# TX_Board.net
KiCad netlist of a schematic drawn in Altium Designer
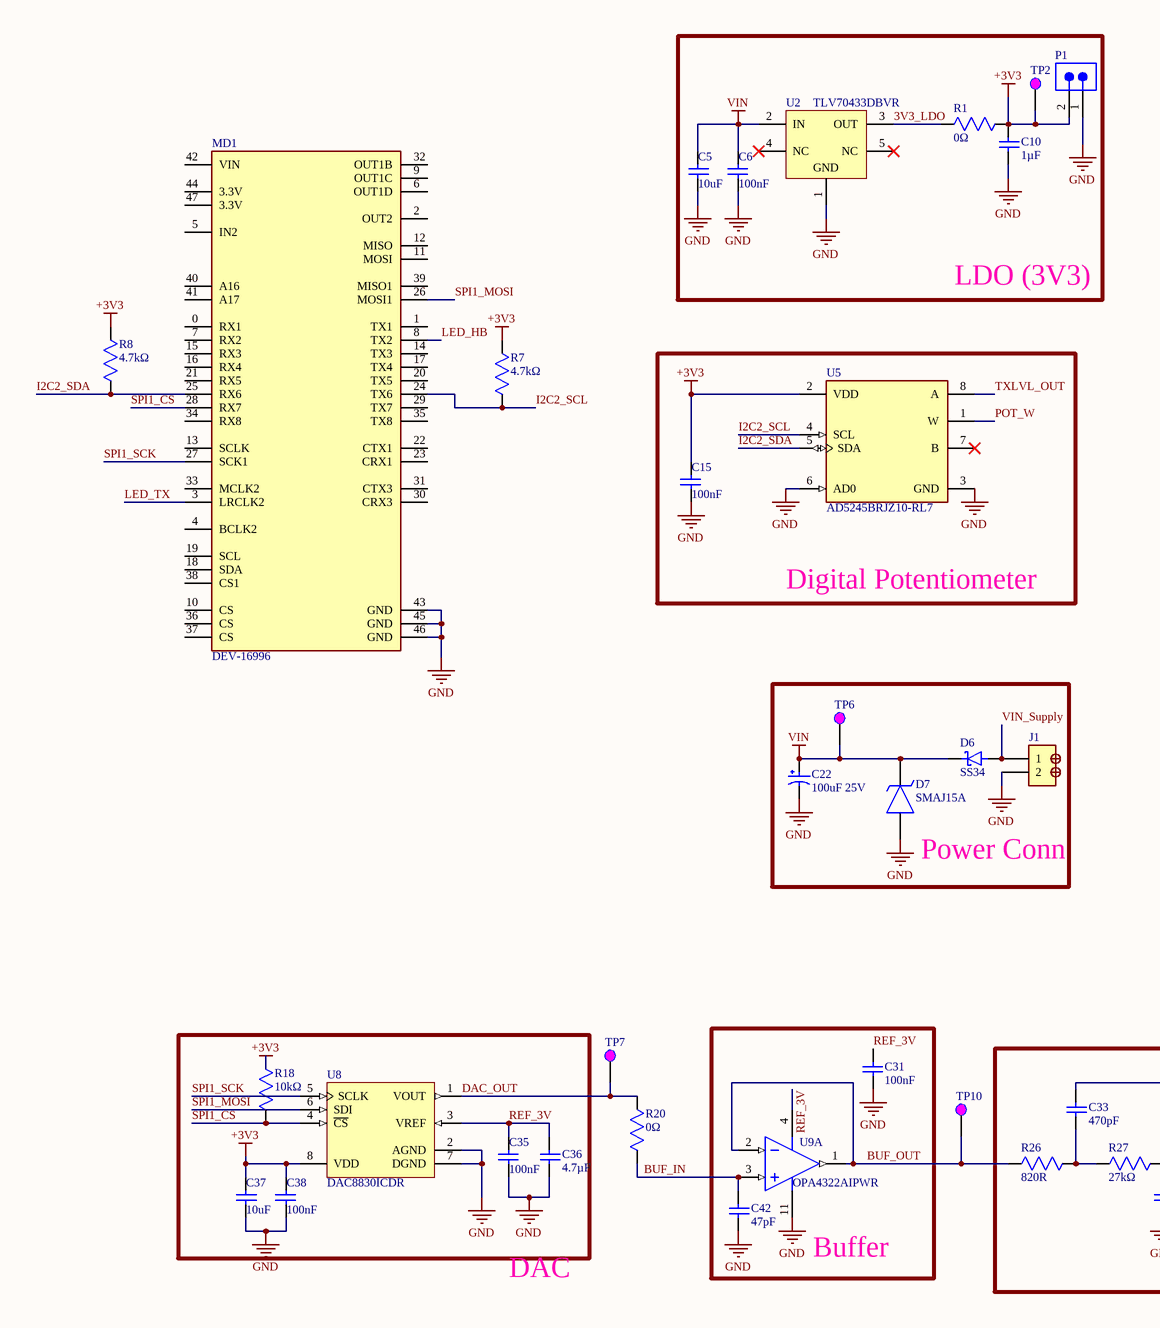
[diagram p0: TX_Board.SchDoc, left]
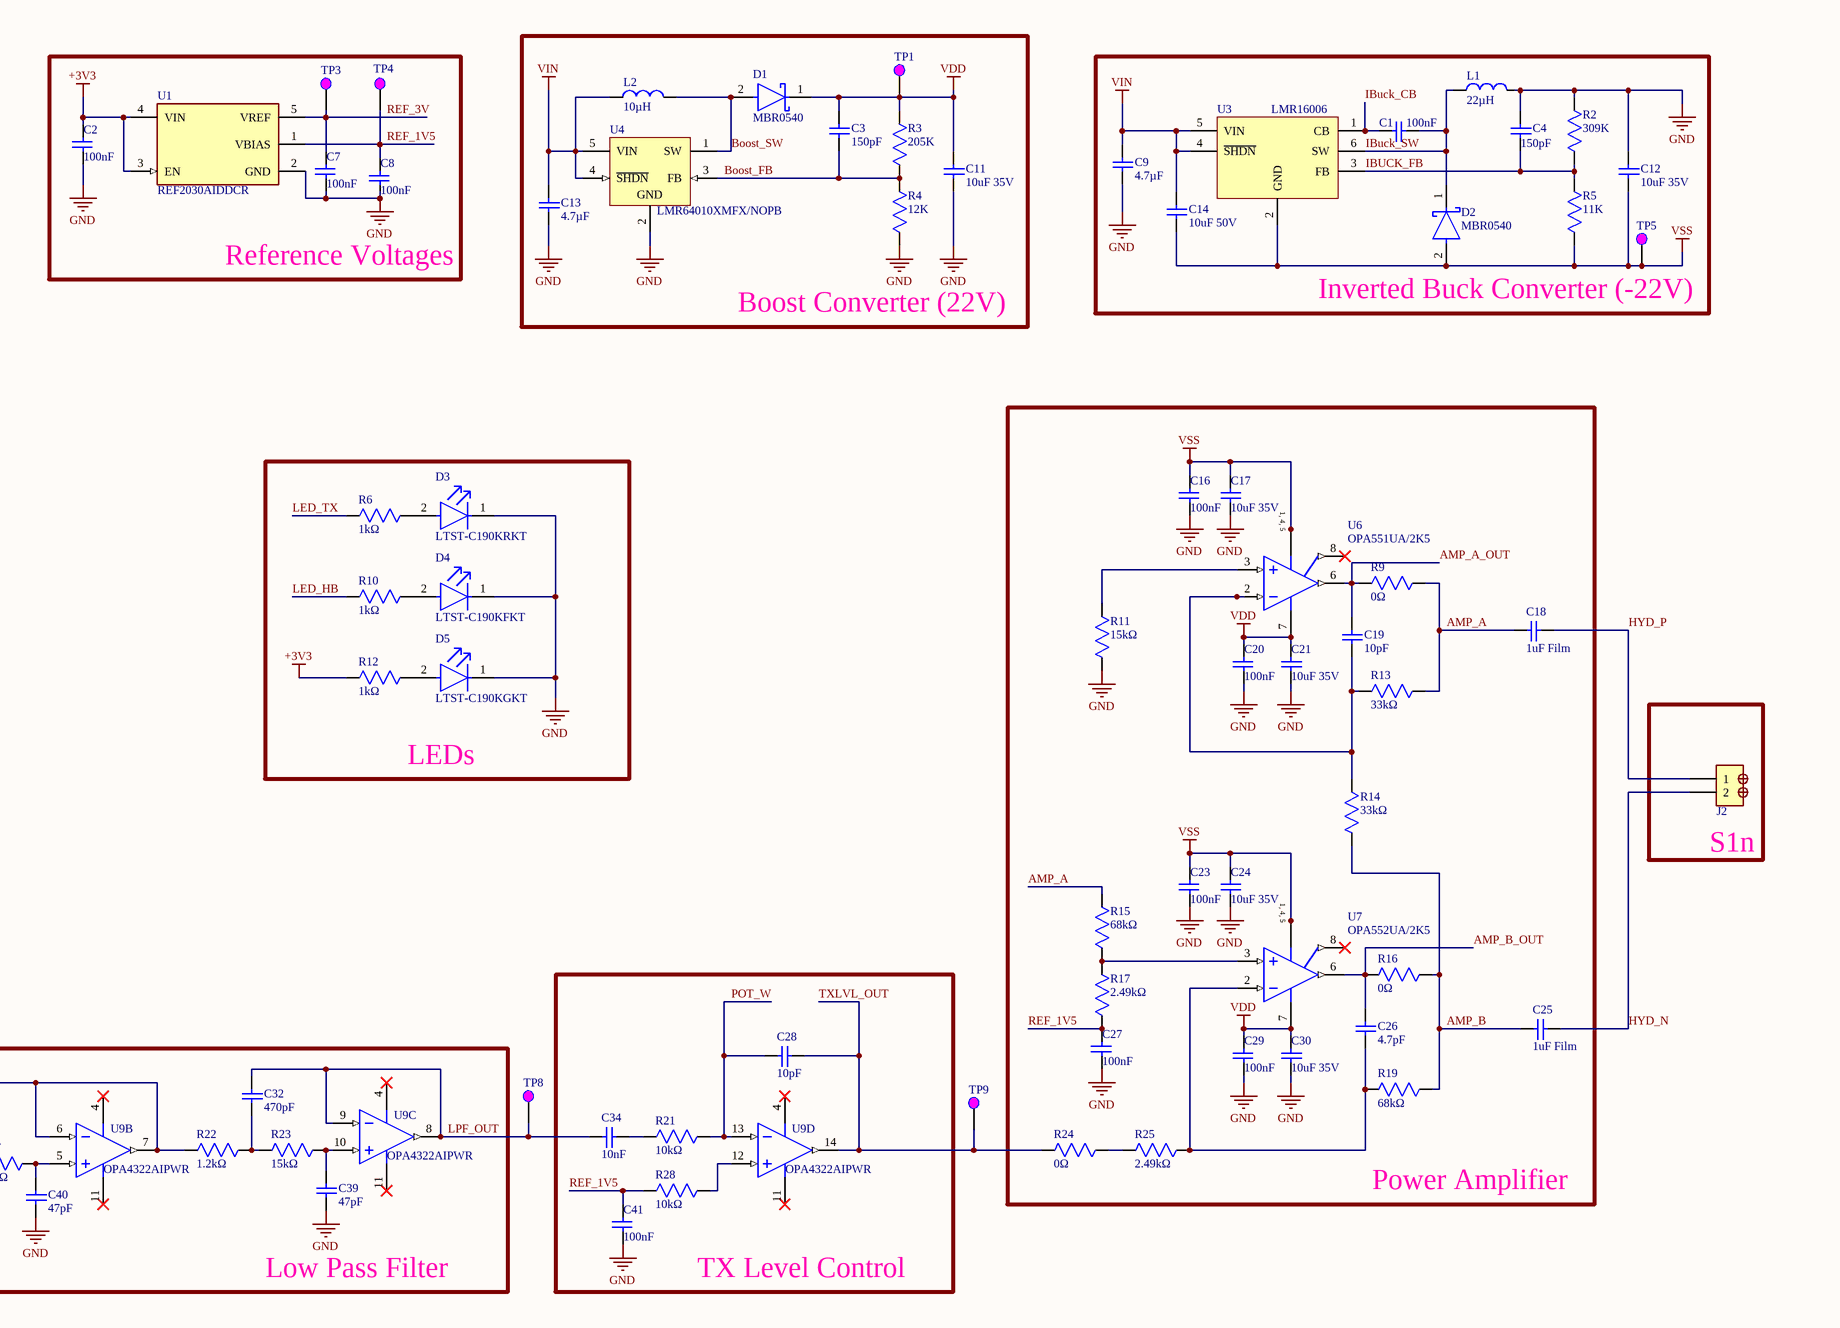
[diagram p1: TX_Board.SchDoc, right]

(export (version "E")
  (design (tool "Eeschema 10.0.6"))
  (components
    (comp (ref "C1")
      (value "100nF")
      (footprint "CAP_0603")
      (description "Multilayer Ceramic Capacitor, CC Series, 0.1 - F, - 10%, X7R, 50 V, 0603 [1608 Metric]")
      (fields
        (field (name "MANUFACTURER") "Yageo Group")
        (field (name "MANUFACTURER PART NUMBER") "CC0603KRX7R9BB104")
      )
      (libsource (lib "Custom_UAM_Parts") (part "CC0603KRX7R9BB104"))
    )
    (comp (ref "C2")
      (value "100nF")
      (footprint "CAP_0603")
      (description "Multilayer Ceramic Capacitor, CC Series, 0.1 - F, - 10%, X7R, 50 V, 0603 [1608 Metric]")
      (fields
        (field (name "MANUFACTURER") "Yageo Group")
        (field (name "MANUFACTURER PART NUMBER") "CC0603KRX7R9BB104")
      )
      (libsource (lib "Custom_UAM_Parts") (part "CC0603KRX7R9BB104"))
    )
    (comp (ref "C3")
      (value "150pF")
      (footprint "CAP_0603")
      (description "Surface Mount Ceramic Multilayer Capacitor 150pF 5% C0G 50V 0603 Paper T/R")
      (fields
        (field (name "MANUFACTURER") "Yageo Group")
        (field (name "MANUFACTURER PART NUMBER") "CC0603JRNPO9BN151")
      )
      (libsource (lib "Custom_UAM_Parts") (part "CC0603JRNPO9BN151"))
    )
    (comp (ref "C4")
      (value "150pF")
      (footprint "CAP_0603")
      (description "Surface Mount Ceramic Multilayer Capacitor 150pF 5% C0G 50V 0603 Paper T/R")
      (fields
        (field (name "MANUFACTURER") "Yageo Group")
        (field (name "MANUFACTURER PART NUMBER") "CC0603JRNPO9BN151")
      )
      (libsource (lib "Custom_UAM_Parts") (part "CC0603JRNPO9BN151"))
    )
    (comp (ref "C5")
      (value "10uF")
      (footprint "CAP_0603")
      (description "25V 10uF X5R ±20% 0603 Multilayer Ceramic Capacitors MLCC - SMD/SMT ROHS")
      (fields
        (field (name "MANUFACTURER") "Samsung Electro-Mechanics")
        (field (name "MANUFACTURER PART NUMBER") "CL10A106MA8NRNC")
      )
      (libsource (lib "Custom_UAM_Parts") (part "CL10A106MA8NRNC"))
    )
    (comp (ref "C6")
      (value "100nF")
      (footprint "CAP_0603")
      (description "Multilayer Ceramic Capacitor, CC Series, 0.1 - F, - 10%, X7R, 50 V, 0603 [1608 Metric]")
      (fields
        (field (name "MANUFACTURER") "Yageo Group")
        (field (name "MANUFACTURER PART NUMBER") "CC0603KRX7R9BB104")
      )
      (libsource (lib "Custom_UAM_Parts") (part "CC0603KRX7R9BB104"))
    )
    (comp (ref "C7")
      (value "100nF")
      (footprint "CAP_0603")
      (description "Multilayer Ceramic Capacitor, CC Series, 0.1 - F, - 10%, X7R, 50 V, 0603 [1608 Metric]")
      (fields
        (field (name "MANUFACTURER") "Yageo Group")
        (field (name "MANUFACTURER PART NUMBER") "CC0603KRX7R9BB104")
      )
      (libsource (lib "Custom_UAM_Parts") (part "CC0603KRX7R9BB104"))
    )
    (comp (ref "C8")
      (value "100nF")
      (footprint "CAP_0603")
      (description "Multilayer Ceramic Capacitor, CC Series, 0.1 - F, - 10%, X7R, 50 V, 0603 [1608 Metric]")
      (fields
        (field (name "MANUFACTURER") "Yageo Group")
        (field (name "MANUFACTURER PART NUMBER") "CC0603KRX7R9BB104")
      )
      (libsource (lib "Custom_UAM_Parts") (part "CC0603KRX7R9BB104"))
    )
    (comp (ref "C9")
      (value "4.7µF")
      (footprint "CAP_0603")
      (description "25V 4.7uF X5R 卤10% 0603 Multilayer Ceramic Capacitors MLCC - SMD/SMT ROHS")
      (fields
        (field (name "MANUFACTURER") "Samsung Electro-Mechanics")
        (field (name "MANUFACTURER PART NUMBER") "CL10A475KA8NQNC")
      )
      (libsource (lib "Custom_UAM_Parts") (part "CL10A475KA8NQNC"))
    )
    (comp (ref "C10")
      (value "1µF")
      (footprint "CAP_0603")
      (description "MLCC - 0603 50 V X7R 1 uF 10 % Multilayer Ceramic Capacitor")
      (fields
        (field (name "MANUFACTURER") "Samsung Electro-Mechanics")
        (field (name "MANUFACTURER PART NUMBER") "CL10B105KB8NQNC")
      )
      (libsource (lib "Custom_UAM_Parts") (part "CL10B105KB8NQNC"))
    )
    (comp (ref "C11")
      (value "10uF 35V")
      (footprint "CAP_0603")
      (description "35V 10uF X5R ±20% 0603 Multilayer Ceramic Capacitors MLCC - SMD/SMT ROHS")
      (fields
        (field (name "MANUFACTURER") "Murata")
        (field (name "MANUFACTURER PART NUMBER") "GRM188R6YA106MA73D")
      )
      (libsource (lib "Custom_UAM_Parts") (part "GRM188R6YA106MA73D"))
    )
    (comp (ref "C12")
      (value "10uF 35V")
      (footprint "CAP_0603")
      (description "35V 10uF X5R ±20% 0603 Multilayer Ceramic Capacitors MLCC - SMD/SMT ROHS")
      (fields
        (field (name "MANUFACTURER") "Murata")
        (field (name "MANUFACTURER PART NUMBER") "GRM188R6YA106MA73D")
      )
      (libsource (lib "Custom_UAM_Parts") (part "GRM188R6YA106MA73D"))
    )
    (comp (ref "C13")
      (value "4.7µF")
      (footprint "CAP_0603")
      (description "25V 4.7uF X5R 卤10% 0603 Multilayer Ceramic Capacitors MLCC - SMD/SMT ROHS")
      (fields
        (field (name "MANUFACTURER") "Samsung Electro-Mechanics")
        (field (name "MANUFACTURER PART NUMBER") "CL10A475KA8NQNC")
      )
      (libsource (lib "Custom_UAM_Parts") (part "CL10A475KA8NQNC"))
    )
    (comp (ref "C14")
      (value "10uF 50V")
      (footprint "CAP_0603")
      (description "50V 10uF X5R ±10% 0805 Multilayer Ceramic Capacitors MLCC - SMD/SMT ROHS")
      (fields
        (field (name "MANUFACTURER") "Murata")
        (field (name "MANUFACTURER PART NUMBER") "GRM21BR61H106KE43L")
      )
      (libsource (lib "Custom_UAM_Parts") (part "GRM21BR61H106KE43L"))
    )
    (comp (ref "C15")
      (value "100nF")
      (footprint "CAP_0603")
      (description "Multilayer Ceramic Capacitor, CC Series, 0.1 - F, - 10%, X7R, 50 V, 0603 [1608 Metric]")
      (fields
        (field (name "MANUFACTURER") "Yageo Group")
        (field (name "MANUFACTURER PART NUMBER") "CC0603KRX7R9BB104")
      )
      (libsource (lib "Custom_UAM_Parts") (part "CC0603KRX7R9BB104"))
    )
    (comp (ref "C16")
      (value "100nF")
      (footprint "CAP_0603")
      (description "Multilayer Ceramic Capacitor, CC Series, 0.1 - F, - 10%, X7R, 50 V, 0603 [1608 Metric]")
      (fields
        (field (name "MANUFACTURER") "Yageo Group")
        (field (name "MANUFACTURER PART NUMBER") "CC0603KRX7R9BB104")
      )
      (libsource (lib "Custom_UAM_Parts") (part "CC0603KRX7R9BB104"))
    )
    (comp (ref "C17")
      (value "10uF 35V")
      (footprint "CAP_0603")
      (description "35V 10uF X5R ±20% 0603 Multilayer Ceramic Capacitors MLCC - SMD/SMT ROHS")
      (fields
        (field (name "MANUFACTURER") "Murata")
        (field (name "MANUFACTURER PART NUMBER") "GRM188R6YA106MA73D")
      )
      (libsource (lib "Custom_UAM_Parts") (part "GRM188R6YA106MA73D"))
    )
    (comp (ref "C18")
      (value "1uF Film")
      (footprint "PE105J2A0502")
      (description "-40℃~+110℃ 100V 1uF Metallized Polyester ±5% Plugin,P=5mm Film Capacitors ROHS")
      (fields (field (name "JLCPCB PART NUMBER") "C390070"))
      (libsource (lib "Custom_UAM_Parts") (part "PE105J2A0502"))
    )
    (comp (ref "C19")
      (value "10pF")
      (footprint "CAP_0603")
      (description "50V 10pF NP0 ±1% 0603 Multilayer Ceramic Capacitors MLCC - SMD/SMT ROHS")
      (fields
        (field (name "MANUFACTURER") "Yageo Group")
        (field (name "MANUFACTURER PART NUMBER") "CC0603FRNPO9BN100")
      )
      (libsource (lib "Custom_UAM_Parts") (part "CC0603FRNPO9BN100"))
    )
    (comp (ref "C20")
      (value "100nF")
      (footprint "CAP_0603")
      (description "Multilayer Ceramic Capacitor, CC Series, 0.1 - F, - 10%, X7R, 50 V, 0603 [1608 Metric]")
      (fields
        (field (name "MANUFACTURER") "Yageo Group")
        (field (name "MANUFACTURER PART NUMBER") "CC0603KRX7R9BB104")
      )
      (libsource (lib "Custom_UAM_Parts") (part "CC0603KRX7R9BB104"))
    )
    (comp (ref "C21")
      (value "10uF 35V")
      (footprint "CAP_0603")
      (description "35V 10uF X5R ±20% 0603 Multilayer Ceramic Capacitors MLCC - SMD/SMT ROHS")
      (fields
        (field (name "MANUFACTURER") "Murata")
        (field (name "MANUFACTURER PART NUMBER") "GRM188R6YA106MA73D")
      )
      (libsource (lib "Custom_UAM_Parts") (part "GRM188R6YA106MA73D"))
    )
    (comp (ref "C22")
      (value "100uF 25V")
      (footprint "SamacSys:CAPAE660X800N")
      (description "Capacitor Polarised")
      (fields
        (field (name "MANUFACTURER_PART_NUMBER") "RVT1E101M0607")
        (field (name "JLCPCB PART NUMBER") "C72477")
      )
      (libsource (lib "Custom_UAM_Parts") (part "RVT1E101M0607"))
    )
    (comp (ref "C23")
      (value "100nF")
      (footprint "CAP_0603")
      (description "Multilayer Ceramic Capacitor, CC Series, 0.1 - F, - 10%, X7R, 50 V, 0603 [1608 Metric]")
      (fields
        (field (name "MANUFACTURER") "Yageo Group")
        (field (name "MANUFACTURER PART NUMBER") "CC0603KRX7R9BB104")
      )
      (libsource (lib "Custom_UAM_Parts") (part "CC0603KRX7R9BB104"))
    )
    (comp (ref "C24")
      (value "10uF 35V")
      (footprint "CAP_0603")
      (description "35V 10uF X5R ±20% 0603 Multilayer Ceramic Capacitors MLCC - SMD/SMT ROHS")
      (fields
        (field (name "MANUFACTURER") "Murata")
        (field (name "MANUFACTURER PART NUMBER") "GRM188R6YA106MA73D")
      )
      (libsource (lib "Custom_UAM_Parts") (part "GRM188R6YA106MA73D"))
    )
    (comp (ref "C25")
      (value "1uF Film")
      (footprint "PE105J2A0502")
      (description "-40℃~+110℃ 100V 1uF Metallized Polyester ±5% Plugin,P=5mm Film Capacitors ROHS")
      (fields (field (name "JLCPCB PART NUMBER") "C390070"))
      (libsource (lib "Custom_UAM_Parts") (part "PE105J2A0502"))
    )
    (comp (ref "C26")
      (value "4.7pF")
      (footprint "CAP_0603")
      (description "Surface Mount Ceramic Multilayer Capacitor 4.7pF 0.25pF C0G 50V 0603 Paper T/R")
      (fields
        (field (name "MANUFACTURER") "Yageo Group")
        (field (name "MANUFACTURER PART NUMBER") "CC0603CRNPO9BN4R7")
      )
      (libsource (lib "Custom_UAM_Parts") (part "CC0603CRNPO9BN4R7"))
    )
    (comp (ref "C27")
      (value "100nF")
      (footprint "CAP_0603")
      (description "Multilayer Ceramic Capacitor, CC Series, 0.1 - F, - 10%, X7R, 50 V, 0603 [1608 Metric]")
      (fields
        (field (name "MANUFACTURER") "Yageo Group")
        (field (name "MANUFACTURER PART NUMBER") "CC0603KRX7R9BB104")
      )
      (libsource (lib "Custom_UAM_Parts") (part "CC0603KRX7R9BB104"))
    )
    (comp (ref "C28")
      (value "10pF")
      (footprint "CAP_0603")
      (description "50V 10pF NP0 ±1% 0603 Multilayer Ceramic Capacitors MLCC - SMD/SMT ROHS")
      (fields
        (field (name "MANUFACTURER") "Yageo Group")
        (field (name "MANUFACTURER PART NUMBER") "CC0603FRNPO9BN100")
      )
      (libsource (lib "Custom_UAM_Parts") (part "CC0603FRNPO9BN100"))
    )
    (comp (ref "C29")
      (value "100nF")
      (footprint "CAP_0603")
      (description "Multilayer Ceramic Capacitor, CC Series, 0.1 - F, - 10%, X7R, 50 V, 0603 [1608 Metric]")
      (fields
        (field (name "MANUFACTURER") "Yageo Group")
        (field (name "MANUFACTURER PART NUMBER") "CC0603KRX7R9BB104")
      )
      (libsource (lib "Custom_UAM_Parts") (part "CC0603KRX7R9BB104"))
    )
    (comp (ref "C30")
      (value "10uF 35V")
      (footprint "CAP_0603")
      (description "35V 10uF X5R ±20% 0603 Multilayer Ceramic Capacitors MLCC - SMD/SMT ROHS")
      (fields
        (field (name "MANUFACTURER") "Murata")
        (field (name "MANUFACTURER PART NUMBER") "GRM188R6YA106MA73D")
      )
      (libsource (lib "Custom_UAM_Parts") (part "GRM188R6YA106MA73D"))
    )
    (comp (ref "C31")
      (value "100nF")
      (footprint "CAP_0603")
      (description "Multilayer Ceramic Capacitor, CC Series, 0.1 - F, - 10%, X7R, 50 V, 0603 [1608 Metric]")
      (fields
        (field (name "MANUFACTURER") "Yageo Group")
        (field (name "MANUFACTURER PART NUMBER") "CC0603KRX7R9BB104")
      )
      (libsource (lib "Custom_UAM_Parts") (part "CC0603KRX7R9BB104"))
    )
    (comp (ref "C32")
      (value "470pF")
      (footprint "CAP_0603")
      (description "50V 470pF NP0 ±1% 0603 Multilayer Ceramic Capacitors MLCC - SMD/SMT ROHS")
      (fields
        (field (name "MANUFACTURER") "Yageo Group")
        (field (name "MANUFACTURER PART NUMBER") "CC0603FRNPO9BN471")
      )
      (libsource (lib "Custom_UAM_Parts") (part "CC0603FRNPO9BN471"))
    )
    (comp (ref "C33")
      (value "470pF")
      (footprint "CAP_0603")
      (description "50V 470pF NP0 ±1% 0603 Multilayer Ceramic Capacitors MLCC - SMD/SMT ROHS")
      (fields
        (field (name "MANUFACTURER") "Yageo Group")
        (field (name "MANUFACTURER PART NUMBER") "CC0603FRNPO9BN471")
      )
      (libsource (lib "Custom_UAM_Parts") (part "CC0603FRNPO9BN471"))
    )
    (comp (ref "C34")
      (value "10nF")
      (footprint "CAP_0603")
      (description "Surface Mount Ceramic Multilayer Capacitor 0.01uF 5% X7R 50V 0603 Paper T/R")
      (fields
        (field (name "MANUFACTURER") "Yageo Group")
        (field (name "MANUFACTURER PART NUMBER") "CC0603JRX7R9BB103")
      )
      (libsource (lib "Custom_UAM_Parts") (part "CC0603JRX7R9BB103"))
    )
    (comp (ref "C35")
      (value "100nF")
      (footprint "CAP_0603")
      (description "Multilayer Ceramic Capacitor, CC Series, 0.1 - F, - 10%, X7R, 50 V, 0603 [1608 Metric]")
      (fields
        (field (name "MANUFACTURER") "Yageo Group")
        (field (name "MANUFACTURER PART NUMBER") "CC0603KRX7R9BB104")
      )
      (libsource (lib "Custom_UAM_Parts") (part "CC0603KRX7R9BB104"))
    )
    (comp (ref "C36")
      (value "4.7µF")
      (footprint "CAP_0603")
      (description "25V 4.7uF X5R 卤10% 0603 Multilayer Ceramic Capacitors MLCC - SMD/SMT ROHS")
      (fields
        (field (name "MANUFACTURER") "Samsung Electro-Mechanics")
        (field (name "MANUFACTURER PART NUMBER") "CL10A475KA8NQNC")
      )
      (libsource (lib "Custom_UAM_Parts") (part "CL10A475KA8NQNC"))
    )
    (comp (ref "C37")
      (value "10uF")
      (footprint "CAP_0603")
      (description "25V 10uF X5R ±20% 0603 Multilayer Ceramic Capacitors MLCC - SMD/SMT ROHS")
      (fields
        (field (name "MANUFACTURER") "Samsung Electro-Mechanics")
        (field (name "MANUFACTURER PART NUMBER") "CL10A106MA8NRNC")
      )
      (libsource (lib "Custom_UAM_Parts") (part "CL10A106MA8NRNC"))
    )
    (comp (ref "C38")
      (value "100nF")
      (footprint "CAP_0603")
      (description "Multilayer Ceramic Capacitor, CC Series, 0.1 - F, - 10%, X7R, 50 V, 0603 [1608 Metric]")
      (fields
        (field (name "MANUFACTURER") "Yageo Group")
        (field (name "MANUFACTURER PART NUMBER") "CC0603KRX7R9BB104")
      )
      (libsource (lib "Custom_UAM_Parts") (part "CC0603KRX7R9BB104"))
    )
    (comp (ref "C39")
      (value "47pF")
      (footprint "CAP_0603")
      (description "Surface Mount Ceramic Multilayer Capacitor 47pF 1% C0G 50V 0603 Paper T/R")
      (fields
        (field (name "MANUFACTURER") "Yageo Group")
        (field (name "MANUFACTURER PART NUMBER") "CC0603FRNPO9BN470")
      )
      (libsource (lib "Custom_UAM_Parts") (part "CC0603FRNPO9BN470"))
    )
    (comp (ref "C40")
      (value "47pF")
      (footprint "CAP_0603")
      (description "Surface Mount Ceramic Multilayer Capacitor 47pF 1% C0G 50V 0603 Paper T/R")
      (fields
        (field (name "MANUFACTURER") "Yageo Group")
        (field (name "MANUFACTURER PART NUMBER") "CC0603FRNPO9BN470")
      )
      (libsource (lib "Custom_UAM_Parts") (part "CC0603FRNPO9BN470"))
    )
    (comp (ref "C41")
      (value "100nF")
      (footprint "CAP_0603")
      (description "Multilayer Ceramic Capacitor, CC Series, 0.1 - F, - 10%, X7R, 50 V, 0603 [1608 Metric]")
      (fields
        (field (name "MANUFACTURER") "Yageo Group")
        (field (name "MANUFACTURER PART NUMBER") "CC0603KRX7R9BB104")
      )
      (libsource (lib "Custom_UAM_Parts") (part "CC0603KRX7R9BB104"))
    )
    (comp (ref "C42")
      (value "47pF")
      (footprint "CAP_0603")
      (description "Surface Mount Ceramic Multilayer Capacitor 47pF 1% C0G 50V 0603 Paper T/R")
      (fields
        (field (name "MANUFACTURER") "Yageo Group")
        (field (name "MANUFACTURER PART NUMBER") "CC0603FRNPO9BN470")
      )
      (libsource (lib "Custom_UAM_Parts") (part "CC0603FRNPO9BN470"))
    )
    (comp (ref "D1")
      (value "MBR0540")
      (footprint "FP-425-04-MFG")
      (description "DIODE SCHOTTKY 40V 500MA SOD123")
      (fields (field (name "JLCPCB PART NUMBER") "C21353"))
      (libsource (lib "Altium Content Vault") (part "1d6ec82d83fb6aee721767c19dac4b9"))
    )
    (comp (ref "D2")
      (value "MBR0540")
      (footprint "FP-425-04-MFG")
      (description "DIODE SCHOTTKY 40V 500MA SOD123")
      (fields (field (name "JLCPCB PART NUMBER") "C21353"))
      (libsource (lib "Altium Content Vault") (part "1d6ec82d83fb6aee721767c19dac4b9"))
    )
    (comp (ref "D3")
      (value "LTST-C190KRKT")
      (footprint "FP-LTST-C190KRKT-MFG")
      (description "LED RED CLEAR CHIP SMD")
      (fields (field (name "JLCPCB PART NUMBER") "C94869"))
      (libsource (lib "Altium Content Vault") (part "8706943c75ba83719d021d2fdc84c58"))
    )
    (comp (ref "D4")
      (value "LTST-C190KFKT")
      (footprint "FP-LTST-C190KFKT-MFG")
      (description "LED ORANGE CLEAR CHIP SMD")
      (fields (field (name "JLCPCB PART NUMBER") "C157740"))
      (libsource (lib "Altium Content Vault") (part "8706943c75ba83719d021d2fdc84c58"))
    )
    (comp (ref "D5")
      (value "LTST-C190KGKT")
      (footprint "FP-LTST-C190KGKT-MFG")
      (description "LED GREEN CLEAR CHIP SMD")
      (fields (field (name "JLCPCB PART NUMBER") "C125094"))
      (libsource (lib "Altium Content Vault") (part "8706943c75ba83719d021d2fdc84c58"))
    )
    (comp (ref "D6")
      (value "SS34")
      (footprint "SS34")
      (description "-55℃~+125℃ 3A 40V 500uA@40V 550mV@3A Independent SMA(DO-214AC) Schottky Diodes ROHS")
      (fields (field (name "MANUFACTURER") "MDD") (field (name "JLCPCB PART NUMBER") "C8678"))
      (libsource (lib "Custom_UAM_Parts") (part "SS34"))
    )
    (comp (ref "D7")
      (value "SMAJ15A")
      (footprint "DIOM5026X229N")
      (description "SMAJ Series 24.4 V 400 W Surface Mount Uni-Directional TVS Diode - DO-214AC")
      (fields (field (name "MANUFACTURER") "Littelfuse") (field (name "JLCPCB PART NUMBER") "C148216"))
      (libsource (lib "Custom_UAM_Parts") (part "SMAJ15A"))
    )
    (comp (ref "J1")
      (value "DB301V-3.5-2P-GN-S")
      (footprint "DB301V-3.5-2P-GN-S")
      (fields (field (name "JLCPCB PART NUMBER") "C695629"))
      (libsource (lib "Custom_UAM_Parts") (part "DB301V-3.5-2P-GN-S"))
    )
    (comp (ref "J2")
      (value "DB301V-3.5-2P-GN-S")
      (footprint "DB301V-3.5-2P-GN-S")
      (fields (field (name "JLCPCB PART NUMBER") "C695629"))
      (libsource (lib "Custom_UAM_Parts") (part "DB301V-3.5-2P-GN-S"))
    )
    (comp (ref "L1")
      (value "22µH")
      (footprint "SWPA5040S100MT")
      (description "General Purpose Inductor, 22uH, 20%, 1 Element, Ferrite-Core, SMD, 2020")
      (fields
        (field (name "MANUFACTURER") "Sunlord")
        (field (name "MANUFACTURER PART NUMBER") "SWPA5040S220MT")
      )
      (libsource (lib "Custom_UAM_Parts") (part "SWPA5040S220MT"))
    )
    (comp (ref "L2")
      (value "10µH")
      (footprint "SWPA5040S100MT")
      (description "General Purpose Inductor, 10uH, 20%, 1 Element, Ferrite-Core, SMD, 2020")
      (fields
        (field (name "MANUFACTURER") "Sunlord")
        (field (name "MANUFACTURER PART NUMBER") "SWPA5040S100MT")
      )
      (libsource (lib "Custom_UAM_Parts") (part "SWPA5040S100MT"))
    )
    (comp (ref "MD1")
      (value "DEV-16996")
      (footprint "FP-DEV-16996-MFG")
      (description "TEENSY 4.1 (HEADERS)")
      (libsource (lib "Altium Content Vault") (part "080115a1ce54750370cf87ec145ee29"))
    )
    (comp (ref "P1")
      (value "61300211121")
      (footprint "61300211121")
      (description "THT Vertical Pin Header WR-PHD, Pitch 2.54 mm, Single Row, 2 pins")
      (libsource (lib "Altium Content Vault") (part "Header_Male_1R_02P"))
    )
    (comp (ref "R1")
      (value "0Ω")
      (footprint "RES_0603")
      (description "Zero Ohm Resistor, Jumper, 0603 [1608 Metric], Thick Film, 100 mW, 1 A, Surface Mount")
      (fields
        (field (name "MANUFACTURER") "Yageo Group")
        (field (name "MANUFACTURER PART NUMBER") "RC0603FR-070RL")
      )
      (libsource (lib "Custom_UAM_Parts") (part "RC0603FR-070RL"))
    )
    (comp (ref "R2")
      (value "309K")
      (footprint "RES_0603")
      (description "Res Thick Film 0603 309K Ohm 1% 0.1W(1/10W) ±100ppm/C Pad SMD T/R")
      (fields
        (field (name "MANUFACTURER") "Yageo Group")
        (field (name "MANUFACTURER PART NUMBER") "RC0603FR-07309KL")
      )
      (libsource (lib "Custom_UAM_Parts") (part "RC0603FR-07309KL"))
    )
    (comp (ref "R3")
      (value "205K")
      (footprint "RES_0603")
      (description "100mW Thin Film Resistor ±50ppm/℃ ±0.1% 205kΩ 0603 Chip Resistor - Surface Mount ROHS")
      (fields
        (field (name "MANUFACTURER") "Yageo Group")
        (field (name "MANUFACTURER PART NUMBER") "RT0603BRE07205KL")
      )
      (libsource (lib "Custom_UAM_Parts") (part "RT0603BRE07205KL"))
    )
    (comp (ref "R4")
      (value "12K")
      (footprint "RES_0603")
      (description "100mW Thick Film Resistors 75V ±100ppm/℃ ±1% 12kΩ 0603 Chip Resistor - Surface Mount ROHS")
      (fields
        (field (name "MANUFACTURER") "Yageo Group")
        (field (name "MANUFACTURER PART NUMBER") "RC0603FR-0712KL")
      )
      (libsource (lib "Custom_UAM_Parts") (part "RC0603FR-0712KL"))
    )
    (comp (ref "R5")
      (value "11K")
      (footprint "RES_0603")
      (description "Res Thick Film 0603 11K Ohm 1% 0.1W(1/10W) ±100ppm/C Pad SMD T/R")
      (fields
        (field (name "MANUFACTURER") "Yageo Group")
        (field (name "MANUFACTURER PART NUMBER") "RC0603FR-0711KL")
      )
      (libsource (lib "Custom_UAM_Parts") (part "RC0603FR-0711KL"))
    )
    (comp (ref "R6")
      (value "1kΩ")
      (footprint "RES_0603")
      (description "Res Thick Film 0603 1K Ohm 1% 0.1W(1/10W) ±100ppm/C Pad SMD T/R")
      (fields
        (field (name "MANUFACTURER") "Royal Ohm")
        (field (name "MANUFACTURER PART NUMBER") "0603WAF1001T5E")
      )
      (libsource (lib "Custom_UAM_Parts") (part "0603WAF1001T5E"))
    )
    (comp (ref "R7")
      (value "4.7kΩ")
      (footprint "RES_0603")
      (description "Yageo RC0603FR-074K7L Resistor 0603 SMD 4.7k Ohm 1% 100mW Thick Film")
      (fields
        (field (name "MANUFACTURER") "Yageo Group")
        (field (name "MANUFACTURER PART NUMBER") "RC0603FR-074K7L")
      )
      (libsource (lib "Custom_UAM_Parts") (part "RC0603FR-074K7L"))
    )
    (comp (ref "R8")
      (value "4.7kΩ")
      (footprint "RES_0603")
      (description "Yageo RC0603FR-074K7L Resistor 0603 SMD 4.7k Ohm 1% 100mW Thick Film")
      (fields
        (field (name "MANUFACTURER") "Yageo Group")
        (field (name "MANUFACTURER PART NUMBER") "RC0603FR-074K7L")
      )
      (libsource (lib "Custom_UAM_Parts") (part "RC0603FR-074K7L"))
    )
    (comp (ref "R9")
      (value "0Ω")
      (footprint "RES_0603")
      (description "Zero Ohm Resistor, Jumper, 0603 [1608 Metric], Thick Film, 100 mW, 1 A, Surface Mount")
      (fields
        (field (name "MANUFACTURER") "Yageo Group")
        (field (name "MANUFACTURER PART NUMBER") "RC0603FR-070RL")
      )
      (libsource (lib "Custom_UAM_Parts") (part "RC0603FR-070RL"))
    )
    (comp (ref "R10")
      (value "1kΩ")
      (footprint "RES_0603")
      (description "Res Thick Film 0603 1K Ohm 1% 0.1W(1/10W) ±100ppm/C Pad SMD T/R")
      (fields
        (field (name "MANUFACTURER") "Royal Ohm")
        (field (name "MANUFACTURER PART NUMBER") "0603WAF1001T5E")
      )
      (libsource (lib "Custom_UAM_Parts") (part "0603WAF1001T5E"))
    )
    (comp (ref "R11")
      (value "15kΩ")
      (footprint "RES_0603")
      (description "100mW Thin Film Resistor 75V ±25ppm/℃ ±0.1% 15kΩ 0603 Chip Resistor - Surface Mount ROHS")
      (fields
        (field (name "MANUFACTURER") "Yageo Group")
        (field (name "MANUFACTURER PART NUMBER") "RT0603BRD0715KL")
      )
      (libsource (lib "Custom_UAM_Parts") (part "RT0603BRD0715KL"))
    )
    (comp (ref "R12")
      (value "1kΩ")
      (footprint "RES_0603")
      (description "Res Thick Film 0603 1K Ohm 1% 0.1W(1/10W) ±100ppm/C Pad SMD T/R")
      (fields
        (field (name "MANUFACTURER") "Royal Ohm")
        (field (name "MANUFACTURER PART NUMBER") "0603WAF1001T5E")
      )
      (libsource (lib "Custom_UAM_Parts") (part "0603WAF1001T5E"))
    )
    (comp (ref "R13")
      (value "33kΩ")
      (footprint "RES_0603")
      (description "Res Thin Film 0603 33K Ohm 0.1% 1/10W ±25ppm/°C Molded SMD SMD Paper T/R")
      (fields
        (field (name "MANUFACTURER") "Yageo Group")
        (field (name "MANUFACTURER PART NUMBER") "RT0603BRD0733KL")
      )
      (libsource (lib "Custom_UAM_Parts") (part "RT0603BRD0733KL"))
    )
    (comp (ref "R14")
      (value "33kΩ")
      (footprint "RES_0603")
      (description "Res Thin Film 0603 33K Ohm 0.1% 1/10W ±25ppm/°C Molded SMD SMD Paper T/R")
      (fields
        (field (name "MANUFACTURER") "Yageo Group")
        (field (name "MANUFACTURER PART NUMBER") "RT0603BRD0733KL")
      )
      (libsource (lib "Custom_UAM_Parts") (part "RT0603BRD0733KL"))
    )
    (comp (ref "R15")
      (value "68kΩ")
      (footprint "RES_0603")
      (description "Res Thin Film 0603 68K Ohm 0.1% 1/10W ±25ppm/°C Molded SMD SMD Paper T/R")
      (fields
        (field (name "MANUFACTURER") "Yageo Group")
        (field (name "MANUFACTURER PART NUMBER") "RT0603BRD0768KL")
      )
      (libsource (lib "Custom_UAM_Parts") (part "RT0603BRD0768KL"))
    )
    (comp (ref "R16")
      (value "0Ω")
      (footprint "RES_0603")
      (description "Zero Ohm Resistor, Jumper, 0603 [1608 Metric], Thick Film, 100 mW, 1 A, Surface Mount")
      (fields
        (field (name "MANUFACTURER") "Yageo Group")
        (field (name "MANUFACTURER PART NUMBER") "RC0603FR-070RL")
      )
      (libsource (lib "Custom_UAM_Parts") (part "RC0603FR-070RL"))
    )
    (comp (ref "R17")
      (value "2.49kΩ")
      (footprint "RES_0603")
      (description "100mW Thin Film Resistor 75V ±50ppm/℃ ±0.1% 2.49kΩ 0603 Chip Resistor - Surface Mount ROHS")
      (fields
        (field (name "MANUFACTURER") "Yageo Group")
        (field (name "MANUFACTURER PART NUMBER") "RT0603BRE072K49L")
      )
      (libsource (lib "Custom_UAM_Parts") (part "RT0603BRE072K49L"))
    )
    (comp (ref "R18")
      (value "10kΩ")
      (footprint "CAP_0603")
      (description "100mW Thick Film Resistors ±100ppm/℃ ±1% 10kΩ 0603 Chip Resistor - Surface Mount ROHS")
      (fields
        (field (name "MANUFACTURER") "Yageo Group")
        (field (name "MANUFACTURER PART NUMBER") "RC0603FR-0710KL")
      )
      (libsource (lib "Custom_UAM_Parts") (part "RC0603FR-0710KL"))
    )
    (comp (ref "R19")
      (value "68kΩ")
      (footprint "RES_0603")
      (description "Res Thin Film 0603 68K Ohm 0.1% 1/10W ±25ppm/°C Molded SMD SMD Paper T/R")
      (fields
        (field (name "MANUFACTURER") "Yageo Group")
        (field (name "MANUFACTURER PART NUMBER") "RT0603BRD0768KL")
      )
      (libsource (lib "Custom_UAM_Parts") (part "RT0603BRD0768KL"))
    )
    (comp (ref "R20")
      (value "0Ω")
      (footprint "RES_0603")
      (description "Zero Ohm Resistor, Jumper, 0603 [1608 Metric], Thick Film, 100 mW, 1 A, Surface Mount")
      (fields
        (field (name "MANUFACTURER") "Yageo Group")
        (field (name "MANUFACTURER PART NUMBER") "RC0603FR-070RL")
      )
      (libsource (lib "Custom_UAM_Parts") (part "RC0603FR-070RL"))
    )
    (comp (ref "R21")
      (value "10kΩ")
      (footprint "CAP_0603")
      (description "100mW Thick Film Resistors ±100ppm/℃ ±1% 10kΩ 0603 Chip Resistor - Surface Mount ROHS")
      (fields
        (field (name "MANUFACTURER") "Yageo Group")
        (field (name "MANUFACTURER PART NUMBER") "RC0603FR-0710KL")
      )
      (libsource (lib "Custom_UAM_Parts") (part "RC0603FR-0710KL"))
    )
    (comp (ref "R22")
      (value "1.2kΩ")
      (footprint "RES_0603")
      (description "100mW Thick Film Resistors 75V ±100ppm/℃ ±1% 1.2kΩ 0603 Chip Resistor - Surface Mount ROHS")
      (fields
        (field (name "MANUFACTURER") "Yageo Group")
        (field (name "MANUFACTURER PART NUMBER") "RC0603FR-071K2L")
      )
      (libsource (lib "Custom_UAM_Parts") (part "RC0603FR-071K2L"))
    )
    (comp (ref "R23")
      (value "15kΩ")
      (footprint "RES_0603")
      (description "100mW Thin Film Resistor 75V ±25ppm/℃ ±0.1% 15kΩ 0603 Chip Resistor - Surface Mount ROHS")
      (fields
        (field (name "MANUFACTURER") "Yageo Group")
        (field (name "MANUFACTURER PART NUMBER") "RT0603BRD0715KL")
      )
      (libsource (lib "Custom_UAM_Parts") (part "RT0603BRD0715KL"))
    )
    (comp (ref "R24")
      (value "0Ω")
      (footprint "RES_0603")
      (description "Zero Ohm Resistor, Jumper, 0603 [1608 Metric], Thick Film, 100 mW, 1 A, Surface Mount")
      (fields
        (field (name "MANUFACTURER") "Yageo Group")
        (field (name "MANUFACTURER PART NUMBER") "RC0603FR-070RL")
      )
      (libsource (lib "Custom_UAM_Parts") (part "RC0603FR-070RL"))
    )
    (comp (ref "R25")
      (value "2.49kΩ")
      (footprint "RES_0603")
      (description "100mW Thin Film Resistor 75V ±50ppm/℃ ±0.1% 2.49kΩ 0603 Chip Resistor - Surface Mount ROHS")
      (fields
        (field (name "MANUFACTURER") "Yageo Group")
        (field (name "MANUFACTURER PART NUMBER") "RT0603BRE072K49L")
      )
      (libsource (lib "Custom_UAM_Parts") (part "RT0603BRE072K49L"))
    )
    (comp (ref "R26")
      (value "820R")
      (footprint "RES_0603")
      (description "100Mw Thick Film Resistors 100Ppm/ 1% 820 0603 Chip Resistor Surface Mount Rohs")
      (fields
        (field (name "MANUFACTURER") "Yageo Group")
        (field (name "MANUFACTURER PART NUMBER") "RC0603FR-07820RL")
      )
      (libsource (lib "Custom_UAM_Parts") (part "RC0603FR-07820RL"))
    )
    (comp (ref "R27")
      (value "27kΩ")
      (footprint "RES_0603")
      (description "100mW Thick Film Resistors 75V ±100ppm/℃ ±1% 27kΩ 0603 Chip Resistor - Surface Mount ROHS")
      (fields
        (field (name "MANUFACTURER") "Yageo Group")
        (field (name "MANUFACTURER PART NUMBER") "RC0603FR-0727KL")
      )
      (libsource (lib "Custom_UAM_Parts") (part "RC0603FR-0727KL"))
    )
    (comp (ref "R28")
      (value "10kΩ")
      (footprint "CAP_0603")
      (description "100mW Thick Film Resistors ±100ppm/℃ ±1% 10kΩ 0603 Chip Resistor - Surface Mount ROHS")
      (fields
        (field (name "MANUFACTURER") "Yageo Group")
        (field (name "MANUFACTURER PART NUMBER") "RC0603FR-0710KL")
      )
      (libsource (lib "Custom_UAM_Parts") (part "RC0603FR-0710KL"))
    )
    (comp (ref "TP1")
      (value "Test Point")
      (footprint "Test Point")
      (libsource (lib "Custom_UAM_Parts") (part "Test Point"))
    )
    (comp (ref "TP2")
      (value "Test Point")
      (footprint "Test Point")
      (libsource (lib "Custom_UAM_Parts") (part "Test Point"))
    )
    (comp (ref "TP3")
      (value "Test Point")
      (footprint "Test Point")
      (libsource (lib "Custom_UAM_Parts") (part "Test Point"))
    )
    (comp (ref "TP4")
      (value "Test Point")
      (footprint "Test Point")
      (libsource (lib "Custom_UAM_Parts") (part "Test Point"))
    )
    (comp (ref "TP5")
      (value "Test Point")
      (footprint "Test Point")
      (libsource (lib "Custom_UAM_Parts") (part "Test Point"))
    )
    (comp (ref "TP6")
      (value "Test Point")
      (footprint "Test Point")
      (libsource (lib "Custom_UAM_Parts") (part "Test Point"))
    )
    (comp (ref "TP7")
      (value "Test Point")
      (footprint "Test Point")
      (libsource (lib "Custom_UAM_Parts") (part "Test Point"))
    )
    (comp (ref "TP8")
      (value "Test Point")
      (footprint "Test Point")
      (libsource (lib "Custom_UAM_Parts") (part "Test Point"))
    )
    (comp (ref "TP9")
      (value "Test Point")
      (footprint "Test Point")
      (libsource (lib "Custom_UAM_Parts") (part "Test Point"))
    )
    (comp (ref "TP10")
      (value "Test Point")
      (footprint "Test Point")
      (libsource (lib "Custom_UAM_Parts") (part "Test Point"))
    )
    (comp (ref "U1")
      (value "REF2030AIDDCR")
      (footprint "FP-DDC0005A-IPC_A")
      (description "IC VREF SERIES 0.05% SOT23-5")
      (fields (field (name "TOLERANCE") "0.05%") (field (name "JLCPCB PART NUMBER") "C528704"))
      (libsource (lib "Altium Content Vault") (part "eb04169d2c01d0ae6cb82840e3d56b1"))
    )
    (comp (ref "U2")
      (value "TLV70433DBVR")
      (footprint "DBV0005A_M")
      (fields (field (name "MANUFACTURER") "Texas Instruments") (field (name "JLCPCB PART NUMBER") "C94917"))
      (libsource (lib "Altium Content Vault") (part "TI-TLV704XXDBV5"))
    )
    (comp (ref "U3")
      (value "LMR16006")
      (footprint "LMR16006YDDCR")
      (description "SIMPLE SWITCHER® 4V to 60V, 600mA Step-Down Regulator with Low Iq 6-SOT-23-THIN -40 to 125")
      (fields
        (field (name "MANUFACTURER") "Texas Instruments")
        (field (name "MANUFACTURER PART NUMBER") "LMR16006YDDCR")
      )
      (libsource (lib "Custom_UAM_Parts") (part "LMR16006YDDCR"))
    )
    (comp (ref "U4")
      (value "LMR64010XMFX/NOPB")
      (footprint "DBV0005A_N")
      (fields (field (name "MANUFACTURER") "Texas Instruments") (field (name "JLCPCB PART NUMBER") "C165138"))
      (libsource (lib "Altium Content Vault") (part "TI-LMR64010-DBV5"))
    )
    (comp (ref "U5")
      (value "AD5245BRJZ10-RL7")
      (footprint "FP-RJ-8-IPC_B")
      (description "IC DGT POT 10KOHM 256TAP SOT23-8")
      (fields (field (name "TOLERANCE") "30%") (field (name "JLCPCB PART NUMBER") "C144256"))
      (libsource (lib "Altium Content Vault") (part "777f9caa62b19d2ac513b26aa3e00a4"))
    )
    (comp (ref "U6")
      (value "OPA551UA/2K5")
      (footprint "D0008A_N")
      (fields (field (name "MANUFACTURER") "Texas Instruments") (field (name "JLCPCB PART NUMBER") "C544592"))
      (libsource (lib "Altium Content Vault") (part "TI-OPA55X-D8"))
    )
    (comp (ref "U7")
      (value "OPA552UA/2K5")
      (footprint "D0008A_N")
      (fields
        (field (name "MANUFACTURER") "Texas Instruments")
        (field (name "JLCPCB PART NUMBER") "C2057473")
      )
      (libsource (lib "Altium Content Vault") (part "TI-OPA55X-D8"))
    )
    (comp (ref "U8")
      (value "DAC8830ICDR")
      (footprint "TI-D8_M")
      (fields (field (name "MANUFACTURER") "Texas Instruments") (field (name "JLCPCB PART NUMBER") "C527455"))
      (libsource (lib "Altium Content Vault") (part "TI-DAC8830_EP-D8"))
    )
    (comp (ref "U9")
      (value "OPA4322AIPWR")
      (footprint "PW0014A_N")
      (fields (field (name "MANUFACTURER") "Texas Instruments") (field (name "JLCPCB PART NUMBER") "C486027"))
      (libsource (lib "Altium Content Vault") (part "TI-OPA16X4_4XXX-14"))
    )
  )
  (nets
    (net (code "1") (name "+3V3") (class "Default")
      (node (ref "C10") (pin "2") (pinfunction "2_2") (pintype "passive"))
      (node (ref "C15") (pin "1") (pinfunction "1_1") (pintype "passive"))
      (node (ref "C2") (pin "1") (pinfunction "1_1") (pintype "passive"))
      (node (ref "C37") (pin "2") (pinfunction "2_2") (pintype "passive"))
      (node (ref "C38") (pin "1") (pinfunction "1_1") (pintype "passive"))
      (node (ref "P1") (pin "2") (pinfunction "2_2") (pintype "passive"))
      (node (ref "R1") (pin "2") (pinfunction "2_2") (pintype "passive"))
      (node (ref "R12") (pin "1") (pinfunction "1_1") (pintype "passive"))
      (node (ref "R18") (pin "2") (pinfunction "2_2") (pintype "passive"))
      (node (ref "R7") (pin "2") (pinfunction "2_2") (pintype "passive"))
      (node (ref "R8") (pin "2") (pinfunction "2_2") (pintype "passive"))
      (node (ref "TP2") (pin "1") (pinfunction "1_1") (pintype "passive"))
      (node (ref "U1") (pin "3") (pinfunction "EN_3") (pintype "input"))
      (node (ref "U1") (pin "4") (pinfunction "VIN_4") (pintype "power_in"))
      (node (ref "U5") (pin "2") (pinfunction "VDD_2") (pintype "power_in"))
      (node (ref "U8") (pin "8") (pinfunction "VDD_8") (pintype "power_in"))
    )
    (net (code "2") (name "/3V3_LDO") (class "Default")
      (node (ref "R1") (pin "1") (pinfunction "1_1") (pintype "passive"))
      (node (ref "U2") (pin "3") (pinfunction "OUT_3") (pintype "power_in"))
    )
    (net (code "3") (name "/AMP_A") (class "Default")
      (node (ref "C18") (pin "1") (pinfunction "1_1") (pintype "passive"))
      (node (ref "R13") (pin "1") (pinfunction "1_1") (pintype "passive"))
      (node (ref "R15") (pin "2") (pinfunction "2_2") (pintype "passive"))
      (node (ref "R9") (pin "2") (pinfunction "2_2") (pintype "passive"))
    )
    (net (code "4") (name "/AMP_A_OUT") (class "Default")
      (node (ref "C19") (pin "2") (pinfunction "2_2") (pintype "passive"))
      (node (ref "R9") (pin "1") (pinfunction "1_1") (pintype "passive"))
      (node (ref "U6") (pin "6") (pinfunction "OUT_6") (pintype "output"))
    )
    (net (code "5") (name "/AMP_B") (class "Default")
      (node (ref "C25") (pin "1") (pinfunction "1_1") (pintype "passive"))
      (node (ref "R14") (pin "1") (pinfunction "1_1") (pintype "passive"))
      (node (ref "R16") (pin "2") (pinfunction "2_2") (pintype "passive"))
      (node (ref "R19") (pin "2") (pinfunction "2_2") (pintype "passive"))
    )
    (net (code "6") (name "/AMP_B_OUT") (class "Default")
      (node (ref "C26") (pin "2") (pinfunction "2_2") (pintype "passive"))
      (node (ref "R16") (pin "1") (pinfunction "1_1") (pintype "passive"))
      (node (ref "U7") (pin "6") (pinfunction "OUT_6") (pintype "output"))
    )
    (net (code "7") (name "/BUF_IN") (class "Default")
      (node (ref "C42") (pin "2") (pinfunction "2_2") (pintype "passive"))
      (node (ref "R20") (pin "2") (pinfunction "2_2") (pintype "passive"))
      (node (ref "U9") (pin "3") (pinfunction "IN_A+_3") (pintype "input"))
    )
    (net (code "8") (name "/BUF_OUT") (class "Default")
      (node (ref "R26") (pin "1") (pinfunction "1_1") (pintype "passive"))
      (node (ref "TP10") (pin "1") (pinfunction "1_1") (pintype "passive"))
      (node (ref "U9") (pin "1") (pinfunction "OUT_A_1") (pintype "output"))
      (node (ref "U9") (pin "2") (pinfunction "IN_A-_2") (pintype "input"))
    )
    (net (code "9") (name "/Boost_FB") (class "Default")
      (node (ref "C3") (pin "1") (pinfunction "1_1") (pintype "passive"))
      (node (ref "R3") (pin "1") (pinfunction "1_1") (pintype "passive"))
      (node (ref "R4") (pin "2") (pinfunction "2_2") (pintype "passive"))
      (node (ref "U4") (pin "3") (pinfunction "FB_3") (pintype "input"))
    )
    (net (code "10") (name "/Boost_SW") (class "Default")
      (node (ref "D1") (pin "2") (pinfunction "A_2") (pintype "passive"))
      (node (ref "L2") (pin "2") (pinfunction "2_2") (pintype "passive"))
      (node (ref "U4") (pin "1") (pinfunction "SW_1") (pintype "power_in"))
    )
    (net (code "11") (name "/DAC_OUT") (class "Default")
      (node (ref "R20") (pin "1") (pinfunction "1_1") (pintype "passive"))
      (node (ref "TP7") (pin "1") (pinfunction "1_1") (pintype "passive"))
      (node (ref "U8") (pin "1") (pinfunction "VOUT_1") (pintype "output"))
    )
    (net (code "12") (name "/HYD_N") (class "Default")
      (node (ref "C25") (pin "2") (pinfunction "2_2") (pintype "passive"))
      (node (ref "J2") (pin "2") (pinfunction "2_2") (pintype "passive"))
    )
    (net (code "13") (name "/HYD_P") (class "Default")
      (node (ref "C18") (pin "2") (pinfunction "2_2") (pintype "passive"))
      (node (ref "J2") (pin "1") (pinfunction "1_1") (pintype "passive"))
    )
    (net (code "14") (name "/I2C2_SCL") (class "Default")
      (node (ref "MD1") (pin "24") (pinfunction "TX6_24") (pintype "passive"))
      (node (ref "R7") (pin "1") (pinfunction "1_1") (pintype "passive"))
      (node (ref "U5") (pin "4") (pinfunction "SCL_4") (pintype "input"))
    )
    (net (code "15") (name "/I2C2_SDA") (class "Default")
      (node (ref "MD1") (pin "25") (pinfunction "RX6_25") (pintype "passive"))
      (node (ref "R8") (pin "1") (pinfunction "1_1") (pintype "passive"))
      (node (ref "U5") (pin "5") (pinfunction "SDA_5") (pintype "bidirectional"))
    )
    (net (code "16") (name "/IBUCK_FB") (class "Default")
      (node (ref "C4") (pin "1") (pinfunction "1_1") (pintype "passive"))
      (node (ref "R2") (pin "1") (pinfunction "1_1") (pintype "passive"))
      (node (ref "R5") (pin "2") (pinfunction "2_2") (pintype "passive"))
      (node (ref "U3") (pin "3") (pinfunction "FB_3") (pintype "passive"))
    )
    (net (code "17") (name "/IBuck_CB") (class "Default")
      (node (ref "C1") (pin "1") (pinfunction "1_1") (pintype "passive"))
      (node (ref "U3") (pin "1") (pinfunction "CB_1") (pintype "passive"))
    )
    (net (code "18") (name "/IBuck_SW") (class "Default")
      (node (ref "C1") (pin "2") (pinfunction "2_2") (pintype "passive"))
      (node (ref "D2") (pin "1") (pinfunction "C_1") (pintype "passive"))
      (node (ref "L1") (pin "1") (pinfunction "1_1") (pintype "passive"))
      (node (ref "U3") (pin "6") (pinfunction "SW_6") (pintype "passive"))
    )
    (net (code "19") (name "/LED_HB") (class "Default")
      (node (ref "MD1") (pin "8") (pinfunction "TX2_8") (pintype "passive"))
      (node (ref "R10") (pin "1") (pinfunction "1_1") (pintype "passive"))
    )
    (net (code "20") (name "/LED_TX") (class "Default")
      (node (ref "MD1") (pin "3") (pinfunction "LRCLK2_3") (pintype "passive"))
      (node (ref "R6") (pin "1") (pinfunction "1_1") (pintype "passive"))
    )
    (net (code "21") (name "/LPF_OUT") (class "Default")
      (node (ref "C32") (pin "2") (pinfunction "2_2") (pintype "passive"))
      (node (ref "C34") (pin "1") (pinfunction "1_1") (pintype "passive"))
      (node (ref "TP8") (pin "1") (pinfunction "1_1") (pintype "passive"))
      (node (ref "U9") (pin "8") (pinfunction "OUT_C_8") (pintype "output"))
      (node (ref "U9") (pin "9") (pinfunction "IN_C-_9") (pintype "input"))
    )
    (net (code "22") (name "/POT_W") (class "Default")
      (node (ref "C28") (pin "1") (pinfunction "1_1") (pintype "passive"))
      (node (ref "R21") (pin "2") (pinfunction "2_2") (pintype "passive"))
      (node (ref "U5") (pin "1") (pinfunction "W_1") (pintype "passive"))
      (node (ref "U9") (pin "13") (pinfunction "IN_D-_13") (pintype "input"))
    )
    (net (code "23") (name "/REF_1V5") (class "Default")
      (node (ref "C27") (pin "1") (pinfunction "1_1") (pintype "passive"))
      (node (ref "C41") (pin "1") (pinfunction "1_1") (pintype "passive"))
      (node (ref "C8") (pin "1") (pinfunction "1_1") (pintype "passive"))
      (node (ref "R17") (pin "1") (pinfunction "1_1") (pintype "passive"))
      (node (ref "R28") (pin "1") (pinfunction "1_1") (pintype "passive"))
      (node (ref "TP4") (pin "1") (pinfunction "1_1") (pintype "passive"))
      (node (ref "U1") (pin "1") (pinfunction "VBIAS_1") (pintype "power_in"))
    )
    (net (code "24") (name "/REF_3V") (class "Default")
      (node (ref "C31") (pin "1") (pinfunction "1_1") (pintype "passive"))
      (node (ref "C35") (pin "1") (pinfunction "1_1") (pintype "passive"))
      (node (ref "C36") (pin "2") (pinfunction "2_2") (pintype "passive"))
      (node (ref "C7") (pin "1") (pinfunction "1_1") (pintype "passive"))
      (node (ref "TP3") (pin "1") (pinfunction "1_1") (pintype "passive"))
      (node (ref "U1") (pin "5") (pinfunction "VREF_5") (pintype "power_in"))
      (node (ref "U8") (pin "3") (pinfunction "VREF_3") (pintype "input"))
      (node (ref "U9") (pin "4") (pinfunction "V+_4") (pintype "power_in"))
    )
    (net (code "25") (name "/SPI1_CS") (class "Default")
      (node (ref "MD1") (pin "28") (pinfunction "RX7_28") (pintype "passive"))
      (node (ref "R18") (pin "1") (pinfunction "1_1") (pintype "passive"))
      (node (ref "U8") (pin "4") (pinfunction "~{CS}_4") (pintype "input"))
    )
    (net (code "26") (name "/SPI1_MOSI") (class "Default")
      (node (ref "MD1") (pin "26") (pinfunction "MOSI1_26") (pintype "passive"))
      (node (ref "U8") (pin "6") (pinfunction "SDI_6") (pintype "input"))
    )
    (net (code "27") (name "/SPI1_SCK") (class "Default")
      (node (ref "MD1") (pin "27") (pinfunction "SCK1_27") (pintype "passive"))
      (node (ref "U8") (pin "5") (pinfunction "SCLK_5") (pintype "input"))
    )
    (net (code "28") (name "/TXLVL_OUT") (class "Default")
      (node (ref "C28") (pin "2") (pinfunction "2_2") (pintype "passive"))
      (node (ref "R24") (pin "1") (pinfunction "1_1") (pintype "passive"))
      (node (ref "TP9") (pin "1") (pinfunction "1_1") (pintype "passive"))
      (node (ref "U5") (pin "8") (pinfunction "A_8") (pintype "passive"))
      (node (ref "U9") (pin "14") (pinfunction "OUT_D_14") (pintype "output"))
    )
    (net (code "29") (name "/VIN_Supply") (class "Default")
      (node (ref "D6") (pin "A") (pinfunction "A_A") (pintype "passive"))
      (node (ref "J1") (pin "1") (pinfunction "1_1") (pintype "passive"))
    )
    (net (code "30") (name "GND") (class "Default")
      (node (ref "C10") (pin "1") (pinfunction "1_1") (pintype "passive"))
      (node (ref "C11") (pin "1") (pinfunction "1_1") (pintype "passive"))
      (node (ref "C12") (pin "2") (pinfunction "2_2") (pintype "passive"))
      (node (ref "C13") (pin "1") (pinfunction "1_1") (pintype "passive"))
      (node (ref "C15") (pin "2") (pinfunction "2_2") (pintype "passive"))
      (node (ref "C16") (pin "2") (pinfunction "2_2") (pintype "passive"))
      (node (ref "C17") (pin "1") (pinfunction "1_1") (pintype "passive"))
      (node (ref "C2") (pin "2") (pinfunction "2_2") (pintype "passive"))
      (node (ref "C20") (pin "2") (pinfunction "2_2") (pintype "passive"))
      (node (ref "C21") (pin "1") (pinfunction "1_1") (pintype "passive"))
      (node (ref "C22") (pin "2") (pinfunction "-_2") (pintype "passive"))
      (node (ref "C23") (pin "2") (pinfunction "2_2") (pintype "passive"))
      (node (ref "C24") (pin "1") (pinfunction "1_1") (pintype "passive"))
      (node (ref "C27") (pin "2") (pinfunction "2_2") (pintype "passive"))
      (node (ref "C29") (pin "2") (pinfunction "2_2") (pintype "passive"))
      (node (ref "C30") (pin "1") (pinfunction "1_1") (pintype "passive"))
      (node (ref "C31") (pin "2") (pinfunction "2_2") (pintype "passive"))
      (node (ref "C35") (pin "2") (pinfunction "2_2") (pintype "passive"))
      (node (ref "C36") (pin "1") (pinfunction "1_1") (pintype "passive"))
      (node (ref "C37") (pin "1") (pinfunction "1_1") (pintype "passive"))
      (node (ref "C38") (pin "2") (pinfunction "2_2") (pintype "passive"))
      (node (ref "C39") (pin "1") (pinfunction "1_1") (pintype "passive"))
      (node (ref "C4") (pin "2") (pinfunction "2_2") (pintype "passive"))
      (node (ref "C40") (pin "1") (pinfunction "1_1") (pintype "passive"))
      (node (ref "C41") (pin "2") (pinfunction "2_2") (pintype "passive"))
      (node (ref "C42") (pin "1") (pinfunction "1_1") (pintype "passive"))
      (node (ref "C5") (pin "1") (pinfunction "1_1") (pintype "passive"))
      (node (ref "C6") (pin "2") (pinfunction "2_2") (pintype "passive"))
      (node (ref "C7") (pin "2") (pinfunction "2_2") (pintype "passive"))
      (node (ref "C8") (pin "2") (pinfunction "2_2") (pintype "passive"))
      (node (ref "C9") (pin "1") (pinfunction "1_1") (pintype "passive"))
      (node (ref "D3") (pin "1") (pinfunction "C_1") (pintype "passive"))
      (node (ref "D4") (pin "1") (pinfunction "C_1") (pintype "passive"))
      (node (ref "D5") (pin "1") (pinfunction "C_1") (pintype "passive"))
      (node (ref "D7") (pin "2") (pinfunction "A_2") (pintype "passive"))
      (node (ref "J1") (pin "2") (pinfunction "2_2") (pintype "passive"))
      (node (ref "L1") (pin "2") (pinfunction "2_2") (pintype "passive"))
      (node (ref "MD1") (pin "43") (pinfunction "GND_43") (pintype "passive"))
      (node (ref "MD1") (pin "45") (pinfunction "GND_45") (pintype "passive"))
      (node (ref "MD1") (pin "46") (pinfunction "GND_46") (pintype "passive"))
      (node (ref "P1") (pin "1") (pinfunction "1_1") (pintype "passive"))
      (node (ref "R11") (pin "1") (pinfunction "1_1") (pintype "passive"))
      (node (ref "R2") (pin "2") (pinfunction "2_2") (pintype "passive"))
      (node (ref "R4") (pin "1") (pinfunction "1_1") (pintype "passive"))
      (node (ref "U1") (pin "2") (pinfunction "GND_2") (pintype "power_in"))
      (node (ref "U2") (pin "1") (pinfunction "GND_1") (pintype "power_in"))
      (node (ref "U4") (pin "2") (pinfunction "GND_2") (pintype "power_in"))
      (node (ref "U5") (pin "3") (pinfunction "GND_3") (pintype "power_in"))
      (node (ref "U5") (pin "6") (pinfunction "AD0_6") (pintype "input"))
      (node (ref "U8") (pin "2") (pinfunction "AGND_2") (pintype "power_in"))
      (node (ref "U8") (pin "7") (pinfunction "DGND_7") (pintype "power_in"))
      (node (ref "U9") (pin "11") (pinfunction "V-_11") (pintype "power_in"))
    )
    (net (code "31") (name "Net-(C32-Pad1)") (class "Default")
      (node (ref "C32") (pin "1") (pinfunction "1_1") (pintype "passive"))
      (node (ref "R22") (pin "2") (pinfunction "2_2") (pintype "passive"))
      (node (ref "R23") (pin "1") (pinfunction "1_1") (pintype "passive"))
    )
    (net (code "32") (name "Net-(C33-Pad1)") (class "Default")
      (node (ref "C33") (pin "1") (pinfunction "1_1") (pintype "passive"))
      (node (ref "R26") (pin "2") (pinfunction "2_2") (pintype "passive"))
      (node (ref "R27") (pin "1") (pinfunction "1_1") (pintype "passive"))
    )
    (net (code "33") (name "Net-(C34-Pad2)") (class "Default")
      (node (ref "C34") (pin "2") (pinfunction "2_2") (pintype "passive"))
      (node (ref "R21") (pin "1") (pinfunction "1_1") (pintype "passive"))
    )
    (net (code "34") (name "Net-(D3-A)") (class "Default")
      (node (ref "D3") (pin "2") (pinfunction "A_2") (pintype "passive"))
      (node (ref "R6") (pin "2") (pinfunction "2_2") (pintype "passive"))
    )
    (net (code "35") (name "Net-(D4-A)") (class "Default")
      (node (ref "D4") (pin "2") (pinfunction "A_2") (pintype "passive"))
      (node (ref "R10") (pin "2") (pinfunction "2_2") (pintype "passive"))
    )
    (net (code "36") (name "Net-(D5-A)") (class "Default")
      (node (ref "D5") (pin "2") (pinfunction "A_2") (pintype "passive"))
      (node (ref "R12") (pin "2") (pinfunction "2_2") (pintype "passive"))
    )
    (net (code "37") (name "Net-(R24-Pad2)") (class "Default")
      (node (ref "R24") (pin "2") (pinfunction "2_2") (pintype "passive"))
      (node (ref "R25") (pin "1") (pinfunction "1_1") (pintype "passive"))
    )
    (net (code "38") (name "Net-(U6-IN+)") (class "Default")
      (node (ref "R11") (pin "2") (pinfunction "2_2") (pintype "passive"))
      (node (ref "U6") (pin "3") (pinfunction "IN+_3") (pintype "input"))
    )
    (net (code "39") (name "Net-(U6-IN-)") (class "Default")
      (node (ref "C19") (pin "1") (pinfunction "1_1") (pintype "passive"))
      (node (ref "R13") (pin "2") (pinfunction "2_2") (pintype "passive"))
      (node (ref "R14") (pin "2") (pinfunction "2_2") (pintype "passive"))
      (node (ref "U6") (pin "2") (pinfunction "IN-_2") (pintype "input"))
    )
    (net (code "40") (name "Net-(U7-IN+)") (class "Default")
      (node (ref "R15") (pin "1") (pinfunction "1_1") (pintype "passive"))
      (node (ref "R17") (pin "2") (pinfunction "2_2") (pintype "passive"))
      (node (ref "U7") (pin "3") (pinfunction "IN+_3") (pintype "input"))
    )
    (net (code "41") (name "Net-(U7-IN-)") (class "Default")
      (node (ref "C26") (pin "1") (pinfunction "1_1") (pintype "passive"))
      (node (ref "R19") (pin "1") (pinfunction "1_1") (pintype "passive"))
      (node (ref "R25") (pin "2") (pinfunction "2_2") (pintype "passive"))
      (node (ref "U7") (pin "2") (pinfunction "IN-_2") (pintype "input"))
    )
    (net (code "42") (name "Net-(U9B-IN_B+)") (class "Default")
      (node (ref "C40") (pin "2") (pinfunction "2_2") (pintype "passive"))
      (node (ref "R27") (pin "2") (pinfunction "2_2") (pintype "passive"))
      (node (ref "U9") (pin "5") (pinfunction "IN_B+_5") (pintype "input"))
    )
    (net (code "43") (name "Net-(U9B-IN_B-)") (class "Default")
      (node (ref "C33") (pin "2") (pinfunction "2_2") (pintype "passive"))
      (node (ref "R22") (pin "1") (pinfunction "1_1") (pintype "passive"))
      (node (ref "U9") (pin "6") (pinfunction "IN_B-_6") (pintype "input"))
      (node (ref "U9") (pin "7") (pinfunction "OUT_B_7") (pintype "output"))
    )
    (net (code "44") (name "Net-(U9C-IN_C+)") (class "Default")
      (node (ref "C39") (pin "2") (pinfunction "2_2") (pintype "passive"))
      (node (ref "R23") (pin "2") (pinfunction "2_2") (pintype "passive"))
      (node (ref "U9") (pin "10") (pinfunction "IN_C+_10") (pintype "input"))
    )
    (net (code "45") (name "Net-(U9D-IN_D+)") (class "Default")
      (node (ref "R28") (pin "2") (pinfunction "2_2") (pintype "passive"))
      (node (ref "U9") (pin "12") (pinfunction "IN_D+_12") (pintype "input"))
    )
    (net (code "46") (name "VDD") (class "Default")
      (node (ref "C11") (pin "2") (pinfunction "2_2") (pintype "passive"))
      (node (ref "C20") (pin "1") (pinfunction "1_1") (pintype "passive"))
      (node (ref "C21") (pin "2") (pinfunction "2_2") (pintype "passive"))
      (node (ref "C29") (pin "1") (pinfunction "1_1") (pintype "passive"))
      (node (ref "C3") (pin "2") (pinfunction "2_2") (pintype "passive"))
      (node (ref "C30") (pin "2") (pinfunction "2_2") (pintype "passive"))
      (node (ref "D1") (pin "1") (pinfunction "C_1") (pintype "passive"))
      (node (ref "R3") (pin "2") (pinfunction "2_2") (pintype "passive"))
      (node (ref "TP1") (pin "1") (pinfunction "1_1") (pintype "passive"))
      (node (ref "U6") (pin "7") (pinfunction "V+_7") (pintype "power_in"))
      (node (ref "U7") (pin "7") (pinfunction "V+_7") (pintype "power_in"))
    )
    (net (code "47") (name "VIN") (class "Default")
      (node (ref "C13") (pin "2") (pinfunction "2_2") (pintype "passive"))
      (node (ref "C14") (pin "2") (pinfunction "2_2") (pintype "passive"))
      (node (ref "C22") (pin "1") (pinfunction "+_1") (pintype "passive"))
      (node (ref "C5") (pin "2") (pinfunction "2_2") (pintype "passive"))
      (node (ref "C6") (pin "1") (pinfunction "1_1") (pintype "passive"))
      (node (ref "C9") (pin "2") (pinfunction "2_2") (pintype "passive"))
      (node (ref "D6") (pin "K") (pinfunction "K_K") (pintype "passive"))
      (node (ref "D7") (pin "1") (pinfunction "K_1") (pintype "passive"))
      (node (ref "L2") (pin "1") (pinfunction "1_1") (pintype "passive"))
      (node (ref "TP6") (pin "1") (pinfunction "1_1") (pintype "passive"))
      (node (ref "U2") (pin "2") (pinfunction "IN_2") (pintype "power_in"))
      (node (ref "U3") (pin "4") (pinfunction "~{SHDN}_4") (pintype "passive"))
      (node (ref "U3") (pin "5") (pinfunction "VIN_5") (pintype "passive"))
      (node (ref "U4") (pin "4") (pinfunction "~{SHDN}_4") (pintype "input"))
      (node (ref "U4") (pin "5") (pinfunction "VIN_5") (pintype "power_in"))
    )
    (net (code "48") (name "VSS") (class "Default")
      (node (ref "C12") (pin "1") (pinfunction "1_1") (pintype "passive"))
      (node (ref "C14") (pin "1") (pinfunction "1_1") (pintype "passive"))
      (node (ref "C16") (pin "1") (pinfunction "1_1") (pintype "passive"))
      (node (ref "C17") (pin "2") (pinfunction "2_2") (pintype "passive"))
      (node (ref "C23") (pin "1") (pinfunction "1_1") (pintype "passive"))
      (node (ref "C24") (pin "2") (pinfunction "2_2") (pintype "passive"))
      (node (ref "D2") (pin "2") (pinfunction "A_2") (pintype "passive"))
      (node (ref "R5") (pin "1") (pinfunction "1_1") (pintype "passive"))
      (node (ref "TP5") (pin "1") (pinfunction "1_1") (pintype "passive"))
      (node (ref "U3") (pin "2") (pinfunction "GND_2") (pintype "passive"))
      (node (ref "U6") (pin "1") (pinfunction "V-_1") (pintype "power_in"))
      (node (ref "U6") (pin "4") (pinfunction "V-_4") (pintype "power_in"))
      (node (ref "U6") (pin "5") (pinfunction "V-_5") (pintype "power_in"))
      (node (ref "U7") (pin "1") (pinfunction "V-_1") (pintype "power_in"))
      (node (ref "U7") (pin "4") (pinfunction "V-_4") (pintype "power_in"))
      (node (ref "U7") (pin "5") (pinfunction "V-_5") (pintype "power_in"))
    )
    (net (code "49") (name "unconnected-(MD1-3.3V-Pad44)") (class "Default")
      (node (ref "MD1") (pin "44") (pinfunction "3.3V_44") (pintype "passive"))
    )
    (net (code "50") (name "unconnected-(MD1-3.3V-Pad47)") (class "Default")
      (node (ref "MD1") (pin "47") (pinfunction "3.3V_47") (pintype "passive"))
    )
    (net (code "51") (name "unconnected-(MD1-A16-Pad40)") (class "Default")
      (node (ref "MD1") (pin "40") (pinfunction "A16_40") (pintype "passive"))
    )
    (net (code "52") (name "unconnected-(MD1-A17-Pad41)") (class "Default")
      (node (ref "MD1") (pin "41") (pinfunction "A17_41") (pintype "passive"))
    )
    (net (code "53") (name "unconnected-(MD1-BCLK2-Pad4)") (class "Default")
      (node (ref "MD1") (pin "4") (pinfunction "BCLK2_4") (pintype "passive"))
    )
    (net (code "54") (name "unconnected-(MD1-CRX1-Pad23)") (class "Default")
      (node (ref "MD1") (pin "23") (pinfunction "CRX1_23") (pintype "passive"))
    )
    (net (code "55") (name "unconnected-(MD1-CRX3-Pad30)") (class "Default")
      (node (ref "MD1") (pin "30") (pinfunction "CRX3_30") (pintype "passive"))
    )
    (net (code "56") (name "unconnected-(MD1-CS-Pad10)") (class "Default")
      (node (ref "MD1") (pin "10") (pinfunction "CS_10") (pintype "passive"))
    )
    (net (code "57") (name "unconnected-(MD1-CS-Pad36)") (class "Default")
      (node (ref "MD1") (pin "36") (pinfunction "CS_36") (pintype "passive"))
    )
    (net (code "58") (name "unconnected-(MD1-CS-Pad37)") (class "Default")
      (node (ref "MD1") (pin "37") (pinfunction "CS_37") (pintype "passive"))
    )
    (net (code "59") (name "unconnected-(MD1-CS1-Pad38)") (class "Default")
      (node (ref "MD1") (pin "38") (pinfunction "CS1_38") (pintype "passive"))
    )
    (net (code "60") (name "unconnected-(MD1-CTX1-Pad22)") (class "Default")
      (node (ref "MD1") (pin "22") (pinfunction "CTX1_22") (pintype "passive"))
    )
    (net (code "61") (name "unconnected-(MD1-CTX3-Pad31)") (class "Default")
      (node (ref "MD1") (pin "31") (pinfunction "CTX3_31") (pintype "passive"))
    )
    (net (code "62") (name "unconnected-(MD1-IN2-Pad5)") (class "Default")
      (node (ref "MD1") (pin "5") (pinfunction "IN2_5") (pintype "passive"))
    )
    (net (code "63") (name "unconnected-(MD1-MCLK2-Pad33)") (class "Default")
      (node (ref "MD1") (pin "33") (pinfunction "MCLK2_33") (pintype "passive"))
    )
    (net (code "64") (name "unconnected-(MD1-MISO-Pad12)") (class "Default")
      (node (ref "MD1") (pin "12") (pinfunction "MISO_12") (pintype "passive"))
    )
    (net (code "65") (name "unconnected-(MD1-MISO1-Pad39)") (class "Default")
      (node (ref "MD1") (pin "39") (pinfunction "MISO1_39") (pintype "passive"))
    )
    (net (code "66") (name "unconnected-(MD1-MOSI-Pad11)") (class "Default")
      (node (ref "MD1") (pin "11") (pinfunction "MOSI_11") (pintype "passive"))
    )
    (net (code "67") (name "unconnected-(MD1-OUT1B-Pad32)") (class "Default")
      (node (ref "MD1") (pin "32") (pinfunction "OUT1B_32") (pintype "passive"))
    )
    (net (code "68") (name "unconnected-(MD1-OUT1C-Pad9)") (class "Default")
      (node (ref "MD1") (pin "9") (pinfunction "OUT1C_9") (pintype "passive"))
    )
    (net (code "69") (name "unconnected-(MD1-OUT1D-Pad6)") (class "Default")
      (node (ref "MD1") (pin "6") (pinfunction "OUT1D_6") (pintype "passive"))
    )
    (net (code "70") (name "unconnected-(MD1-OUT2-Pad2)") (class "Default")
      (node (ref "MD1") (pin "2") (pinfunction "OUT2_2") (pintype "passive"))
    )
    (net (code "71") (name "unconnected-(MD1-RX1-Pad0)") (class "Default")
      (node (ref "MD1") (pin "0") (pinfunction "RX1_0") (pintype "passive"))
    )
    (net (code "72") (name "unconnected-(MD1-RX2-Pad7)") (class "Default")
      (node (ref "MD1") (pin "7") (pinfunction "RX2_7") (pintype "passive"))
    )
    (net (code "73") (name "unconnected-(MD1-RX3-Pad15)") (class "Default")
      (node (ref "MD1") (pin "15") (pinfunction "RX3_15") (pintype "passive"))
    )
    (net (code "74") (name "unconnected-(MD1-RX4-Pad16)") (class "Default")
      (node (ref "MD1") (pin "16") (pinfunction "RX4_16") (pintype "passive"))
    )
    (net (code "75") (name "unconnected-(MD1-RX5-Pad21)") (class "Default")
      (node (ref "MD1") (pin "21") (pinfunction "RX5_21") (pintype "passive"))
    )
    (net (code "76") (name "unconnected-(MD1-RX8-Pad34)") (class "Default")
      (node (ref "MD1") (pin "34") (pinfunction "RX8_34") (pintype "passive"))
    )
    (net (code "77") (name "unconnected-(MD1-SCL-Pad19)") (class "Default")
      (node (ref "MD1") (pin "19") (pinfunction "SCL_19") (pintype "passive"))
    )
    (net (code "78") (name "unconnected-(MD1-SCLK-Pad13)") (class "Default")
      (node (ref "MD1") (pin "13") (pinfunction "SCLK_13") (pintype "passive"))
    )
    (net (code "79") (name "unconnected-(MD1-SDA-Pad18)") (class "Default")
      (node (ref "MD1") (pin "18") (pinfunction "SDA_18") (pintype "passive"))
    )
    (net (code "80") (name "unconnected-(MD1-TX1-Pad1)") (class "Default")
      (node (ref "MD1") (pin "1") (pinfunction "TX1_1") (pintype "passive"))
    )
    (net (code "81") (name "unconnected-(MD1-TX3-Pad14)") (class "Default")
      (node (ref "MD1") (pin "14") (pinfunction "TX3_14") (pintype "passive"))
    )
    (net (code "82") (name "unconnected-(MD1-TX4-Pad17)") (class "Default")
      (node (ref "MD1") (pin "17") (pinfunction "TX4_17") (pintype "passive"))
    )
    (net (code "83") (name "unconnected-(MD1-TX5-Pad20)") (class "Default")
      (node (ref "MD1") (pin "20") (pinfunction "TX5_20") (pintype "passive"))
    )
    (net (code "84") (name "unconnected-(MD1-TX7-Pad29)") (class "Default")
      (node (ref "MD1") (pin "29") (pinfunction "TX7_29") (pintype "passive"))
    )
    (net (code "85") (name "unconnected-(MD1-TX8-Pad35)") (class "Default")
      (node (ref "MD1") (pin "35") (pinfunction "TX8_35") (pintype "passive"))
    )
    (net (code "86") (name "unconnected-(MD1-VIN-Pad42)") (class "Default")
      (node (ref "MD1") (pin "42") (pinfunction "VIN_42") (pintype "passive"))
    )
    (net (code "87") (name "unconnected-(U2-NC-Pad4)") (class "Default")
      (node (ref "U2") (pin "4") (pinfunction "NC_4") (pintype "passive+no_connect"))
    )
    (net (code "88") (name "unconnected-(U2-NC-Pad5)") (class "Default")
      (node (ref "U2") (pin "5") (pinfunction "NC_5") (pintype "passive+no_connect"))
    )
    (net (code "89") (name "unconnected-(U5-B-Pad7)") (class "Default")
      (node (ref "U5") (pin "7") (pinfunction "B_7") (pintype "passive+no_connect"))
    )
    (net (code "90") (name "unconnected-(U6-FLAG-Pad8)") (class "Default")
      (node (ref "U6") (pin "8") (pinfunction "FLAG_8") (pintype "output+no_connect"))
    )
    (net (code "91") (name "unconnected-(U7-FLAG-Pad8)") (class "Default")
      (node (ref "U7") (pin "8") (pinfunction "FLAG_8") (pintype "output+no_connect"))
    )
    (net (code "92") (name "unconnected-(U9B-V+-Pad4)") (class "Default")
      (node (ref "U9") (pin "4") (pinfunction "V+_4") (pintype "power_in+no_connect"))
    )
    (net (code "93") (name "unconnected-(U9B-V--Pad11)") (class "Default")
      (node (ref "U9") (pin "11") (pinfunction "V-_11") (pintype "power_in+no_connect"))
    )
    (net (code "94") (name "unconnected-(U9C-V+-Pad4)") (class "Default")
      (node (ref "U9") (pin "4") (pinfunction "V+_4") (pintype "power_in+no_connect"))
    )
    (net (code "95") (name "unconnected-(U9C-V--Pad11)") (class "Default")
      (node (ref "U9") (pin "11") (pinfunction "V-_11") (pintype "power_in+no_connect"))
    )
    (net (code "96") (name "unconnected-(U9D-V+-Pad4)") (class "Default")
      (node (ref "U9") (pin "4") (pinfunction "V+_4") (pintype "power_in+no_connect"))
    )
    (net (code "97") (name "unconnected-(U9D-V--Pad11)") (class "Default")
      (node (ref "U9") (pin "11") (pinfunction "V-_11") (pintype "power_in+no_connect"))
    )
  )
)
